# Motor_Control.net
KiCad netlist of a schematic drawn in EAGLE
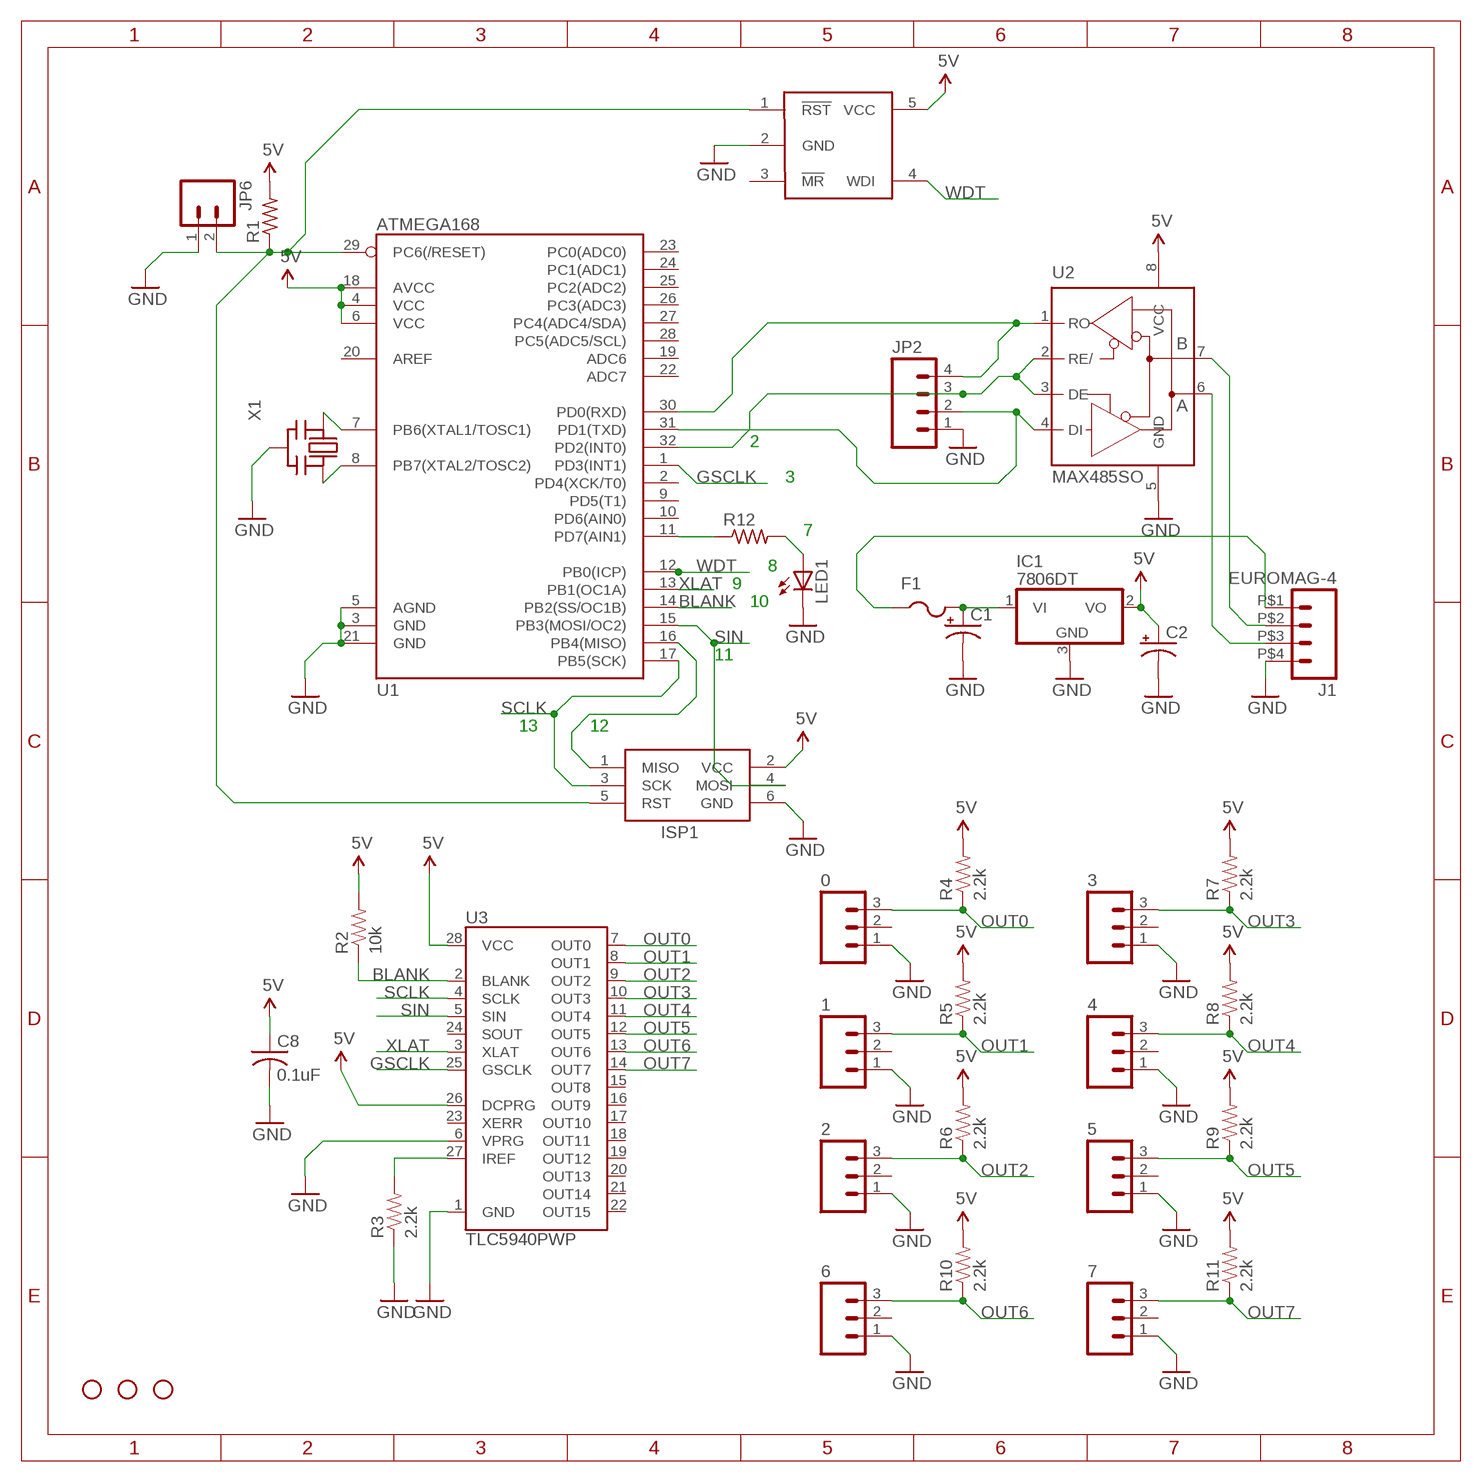
[diagram p0: schematic, sheet 1]
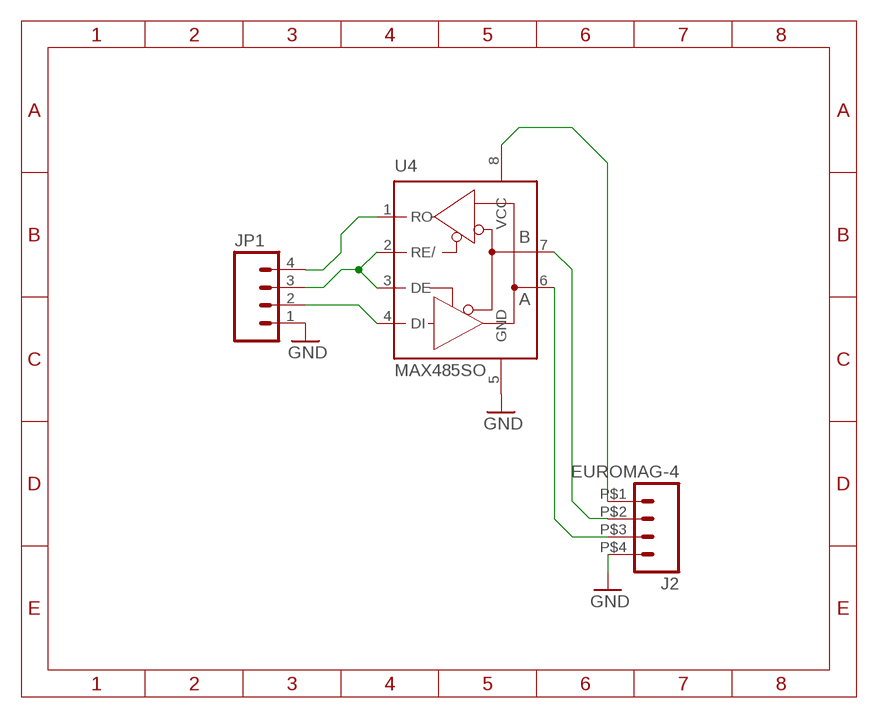
[diagram p1: schematic, sheet 2]

(export (version "E")
  (design (tool "Eeschema 10.0.6"))
  (components
    (comp (ref "0")
      (value "M03PTH")
      (footprint "eagle-import:1X03")
      (libsource (lib "eagle-import") (part "M03PTH"))
    )
    (comp (ref "1")
      (value "M03PTH")
      (footprint "eagle-import:1X03")
      (libsource (lib "eagle-import") (part "M03PTH"))
    )
    (comp (ref "2")
      (value "M03PTH")
      (footprint "eagle-import:1X03")
      (libsource (lib "eagle-import") (part "M03PTH"))
    )
    (comp (ref "3")
      (value "M03PTH")
      (footprint "eagle-import:1X03")
      (libsource (lib "eagle-import") (part "M03PTH"))
    )
    (comp (ref "4")
      (value "M03PTH")
      (footprint "eagle-import:1X03")
      (libsource (lib "eagle-import") (part "M03PTH"))
    )
    (comp (ref "5")
      (value "M03PTH")
      (footprint "eagle-import:1X03")
      (libsource (lib "eagle-import") (part "M03PTH"))
    )
    (comp (ref "6")
      (value "M03PTH")
      (footprint "eagle-import:1X03")
      (libsource (lib "eagle-import") (part "M03PTH"))
    )
    (comp (ref "7")
      (value "M03PTH")
      (footprint "eagle-import:1X03")
      (libsource (lib "eagle-import") (part "M03PTH"))
    )
    (comp (ref "C1")
      (value "CPOL-USCT7343")
      (footprint "eagle-import:CT7343")
      (libsource (lib "eagle-import") (part "CPOL-USCT7343"))
    )
    (comp (ref "C2")
      (value "CPOL-USCT6032")
      (footprint "eagle-import:CT6032")
      (libsource (lib "eagle-import") (part "CPOL-USCT6032"))
    )
    (comp (ref "C8")
      (value "0.1uF")
      (footprint "eagle-import:C0603")
      (libsource (lib "eagle-import") (part "C-USC0603"))
    )
    (comp (ref "F1")
      (value "PTCFUSE-1812")
      (footprint "eagle-import:1812")
      (libsource (lib "eagle-import") (part "PTCFUSE-1812"))
    )
    (comp (ref "IC1")
      (value "7806DT")
      (footprint "eagle-import:TO252")
      (libsource (lib "eagle-import") (part "78DT06"))
    )
    (comp (ref "ISP1")
      (value "AVRISP-6")
      (footprint "eagle-import:AVRISP")
      (libsource (lib "eagle-import") (part "AVRISP-6"))
    )
    (comp (ref "J1")
      (value "EUROMAG-4")
      (footprint "eagle-import:M4")
      (libsource (lib "eagle-import") (part "EUROMAG-4"))
    )
    (comp (ref "JP2")
      (value "M04PTH")
      (footprint "eagle-import:1X04")
      (libsource (lib "eagle-import") (part "M04PTH"))
    )
    (comp (ref "JP3")
      (value "STAND-OFF")
      (footprint "eagle-import:STAND-OFF")
      (libsource (lib "eagle-import") (part "STAND-OFF"))
    )
    (comp (ref "JP4")
      (value "STAND-OFF")
      (footprint "eagle-import:STAND-OFF")
      (libsource (lib "eagle-import") (part "STAND-OFF"))
    )
    (comp (ref "JP5")
      (value "STAND-OFF")
      (footprint "eagle-import:STAND-OFF")
      (libsource (lib "eagle-import") (part "STAND-OFF"))
    )
    (comp (ref "JP6")
      (value "M02LOCK_LONGPADS")
      (footprint "eagle-import:1X02_LOCK_LONGPADS")
      (libsource (lib "eagle-import") (part "M02LOCK_LONGPADS"))
    )
    (comp (ref "LED1")
      (value "LEDCHIPLED_0805")
      (footprint "eagle-import:CHIPLED_0805")
      (libsource (lib "eagle-import") (part "LEDCHIPLED_0805"))
    )
    (comp (ref "R1")
      (value "R-US_M0805")
      (footprint "eagle-import:M0805")
      (libsource (lib "eagle-import") (part "R-US_M0805"))
    )
    (comp (ref "R2")
      (value "10k")
      (footprint "eagle-import:0805")
      (libsource (lib "eagle-import") (part "RESISTOR0805-RES"))
    )
    (comp (ref "R3")
      (value "2.2k")
      (footprint "eagle-import:0805")
      (libsource (lib "eagle-import") (part "RESISTOR0805-RES"))
    )
    (comp (ref "R4")
      (value "2.2k")
      (footprint "eagle-import:0805")
      (libsource (lib "eagle-import") (part "RESISTOR0805-RES"))
    )
    (comp (ref "R5")
      (value "2.2k")
      (footprint "eagle-import:0805")
      (libsource (lib "eagle-import") (part "RESISTOR0805-RES"))
    )
    (comp (ref "R6")
      (value "2.2k")
      (footprint "eagle-import:0805")
      (libsource (lib "eagle-import") (part "RESISTOR0805-RES"))
    )
    (comp (ref "R7")
      (value "2.2k")
      (footprint "eagle-import:0805")
      (libsource (lib "eagle-import") (part "RESISTOR0805-RES"))
    )
    (comp (ref "R8")
      (value "2.2k")
      (footprint "eagle-import:0805")
      (libsource (lib "eagle-import") (part "RESISTOR0805-RES"))
    )
    (comp (ref "R9")
      (value "2.2k")
      (footprint "eagle-import:0805")
      (libsource (lib "eagle-import") (part "RESISTOR0805-RES"))
    )
    (comp (ref "R10")
      (value "2.2k")
      (footprint "eagle-import:0805")
      (libsource (lib "eagle-import") (part "RESISTOR0805-RES"))
    )
    (comp (ref "R11")
      (value "2.2k")
      (footprint "eagle-import:0805")
      (libsource (lib "eagle-import") (part "RESISTOR0805-RES"))
    )
    (comp (ref "R12")
      (value "R-US_M0805")
      (footprint "eagle-import:M0805")
      (libsource (lib "eagle-import") (part "R-US_M0805"))
    )
    (comp (ref "U$18")
      (value "MAX823")
      (footprint "eagle-import:SOT23-5L")
      (libsource (lib "eagle-import") (part "MAX823"))
    )
    (comp (ref "U1")
      (value "ATMEGA168")
      (footprint "eagle-import:TQFP32-08")
      (libsource (lib "eagle-import") (part "ATMEGA168"))
    )
    (comp (ref "U2")
      (value "MAX485SO")
      (footprint "eagle-import:SO08")
      (libsource (lib "eagle-import") (part "MAX485SO"))
    )
    (comp (ref "U3")
      (value "TLC5940PWP")
      (footprint "eagle-import:TSSOP28-GROUNDPAD")
      (libsource (lib "eagle-import") (part "TLC5940PWP"))
    )
    (comp (ref "X1")
      (value "CERMOSCILL-AWCSR")
      (footprint "eagle-import:AWCSR")
      (libsource (lib "eagle-import") (part "CERMOSCILL-AWCSR"))
    )
    (comp (ref "J2")
      (value "EUROMAG-4")
      (footprint "eagle-import:M4")
      (libsource (lib "eagle-import") (part "EUROMAG-4"))
    )
    (comp (ref "JP1")
      (value "M04PTH")
      (footprint "eagle-import:1X04")
      (libsource (lib "eagle-import") (part "M04PTH"))
    )
    (comp (ref "U4")
      (value "MAX485SO")
      (footprint "eagle-import:SO08")
      (libsource (lib "eagle-import") (part "MAX485SO"))
    )
  )
  (nets
    (net (code "1") (name "5V") (class "Default")
      (node (ref "C2") (pin "+") (pinfunction "+_+") (pintype "passive"))
      (node (ref "C8") (pin "1") (pinfunction "1_1") (pintype "passive"))
      (node (ref "IC1") (pin "2") (pinfunction "VO_2") (pintype "passive"))
      (node (ref "ISP1") (pin "2") (pinfunction "VCC_2") (pintype "power_in"))
      (node (ref "R1") (pin "2") (pinfunction "2_2") (pintype "passive"))
      (node (ref "R10") (pin "2") (pinfunction "2_2") (pintype "passive"))
      (node (ref "R11") (pin "2") (pinfunction "2_2") (pintype "passive"))
      (node (ref "R2") (pin "2") (pinfunction "2_2") (pintype "passive"))
      (node (ref "R4") (pin "2") (pinfunction "2_2") (pintype "passive"))
      (node (ref "R5") (pin "2") (pinfunction "2_2") (pintype "passive"))
      (node (ref "R6") (pin "2") (pinfunction "2_2") (pintype "passive"))
      (node (ref "R7") (pin "2") (pinfunction "2_2") (pintype "passive"))
      (node (ref "R8") (pin "2") (pinfunction "2_2") (pintype "passive"))
      (node (ref "R9") (pin "2") (pinfunction "2_2") (pintype "passive"))
      (node (ref "U$18") (pin "5") (pinfunction "VCC_5") (pintype "bidirectional"))
      (node (ref "U1") (pin "18") (pinfunction "AVCC_18") (pintype "bidirectional"))
      (node (ref "U1") (pin "4") (pinfunction "VCC_4") (pintype "bidirectional"))
      (node (ref "U1") (pin "6") (pinfunction "VCC_6") (pintype "bidirectional"))
      (node (ref "U2") (pin "8") (pinfunction "VCC_8") (pintype "bidirectional"))
      (node (ref "U3") (pin "26") (pinfunction "DCPRG_26") (pintype "bidirectional"))
      (node (ref "U3") (pin "28") (pinfunction "VCC_28") (pintype "bidirectional"))
    )
    (net (code "2") (name "BLANK") (class "Default")
      (node (ref "R2") (pin "1") (pinfunction "1_1") (pintype "passive"))
      (node (ref "U1") (pin "14") (pinfunction "PB2(SS/OC1B)_14") (pintype "bidirectional"))
      (node (ref "U3") (pin "2") (pinfunction "BLANK_2") (pintype "bidirectional"))
    )
    (net (code "3") (name "GND") (class "Default")
      (node (ref "0") (pin "1") (pinfunction "1_1") (pintype "passive"))
      (node (ref "1") (pin "1") (pinfunction "1_1") (pintype "passive"))
      (node (ref "2") (pin "1") (pinfunction "1_1") (pintype "passive"))
      (node (ref "3") (pin "1") (pinfunction "1_1") (pintype "passive"))
      (node (ref "4") (pin "1") (pinfunction "1_1") (pintype "passive"))
      (node (ref "5") (pin "1") (pinfunction "1_1") (pintype "passive"))
      (node (ref "6") (pin "1") (pinfunction "1_1") (pintype "passive"))
      (node (ref "7") (pin "1") (pinfunction "1_1") (pintype "passive"))
      (node (ref "C1") (pin "-") (pinfunction "-_-") (pintype "passive"))
      (node (ref "C2") (pin "-") (pinfunction "-_-") (pintype "passive"))
      (node (ref "C8") (pin "2") (pinfunction "2_2") (pintype "passive"))
      (node (ref "IC1") (pin "3") (pinfunction "GND_3") (pintype "passive"))
      (node (ref "ISP1") (pin "6") (pinfunction "GND_6") (pintype "power_in"))
      (node (ref "J1") (pin "P$4") (pinfunction "4_P$4") (pintype "passive"))
      (node (ref "J2") (pin "P$4") (pinfunction "4_P$4") (pintype "passive"))
      (node (ref "JP1") (pin "1") (pinfunction "1_1") (pintype "passive"))
      (node (ref "JP2") (pin "1") (pinfunction "1_1") (pintype "passive"))
      (node (ref "JP6") (pin "1") (pinfunction "1_1") (pintype "passive"))
      (node (ref "LED1") (pin "C") (pinfunction "C_C") (pintype "passive"))
      (node (ref "R3") (pin "1") (pinfunction "1_1") (pintype "passive"))
      (node (ref "U$18") (pin "2") (pinfunction "GND_2") (pintype "bidirectional"))
      (node (ref "U1") (pin "21") (pinfunction "GND_21") (pintype "bidirectional"))
      (node (ref "U1") (pin "3") (pinfunction "GND_3") (pintype "bidirectional"))
      (node (ref "U1") (pin "5") (pinfunction "AGND_5") (pintype "bidirectional"))
      (node (ref "U2") (pin "5") (pinfunction "GND_5") (pintype "bidirectional"))
      (node (ref "U3") (pin "1") (pinfunction "GND_1") (pintype "bidirectional"))
      (node (ref "U3") (pin "6") (pinfunction "VPRG_6") (pintype "bidirectional"))
      (node (ref "U4") (pin "5") (pinfunction "GND_5") (pintype "bidirectional"))
      (node (ref "X1") (pin "2") (pinfunction "GND_2") (pintype "bidirectional"))
    )
    (net (code "4") (name "GSCLK") (class "Default")
      (node (ref "U1") (pin "1") (pinfunction "PD3(INT1)_1") (pintype "bidirectional"))
      (node (ref "U3") (pin "25") (pinfunction "GSCLK_25") (pintype "bidirectional"))
    )
    (net (code "5") (name "Net-(IC1-VI)") (class "Default")
      (node (ref "C1") (pin "+") (pinfunction "+_+") (pintype "passive"))
      (node (ref "F1") (pin "2") (pinfunction "2_2") (pintype "passive"))
      (node (ref "IC1") (pin "1") (pinfunction "VI_1") (pintype "input"))
    )
    (net (code "6") (name "Net-(ISP1-MISO)") (class "Default")
      (node (ref "ISP1") (pin "1") (pinfunction "MISO_1") (pintype "input"))
      (node (ref "U1") (pin "16") (pinfunction "PB4(MISO)_16") (pintype "bidirectional"))
    )
    (net (code "7") (name "Net-(ISP1-RST)") (class "Default")
      (node (ref "ISP1") (pin "5") (pinfunction "RST_5") (pintype "output"))
      (node (ref "JP6") (pin "2") (pinfunction "2_2") (pintype "passive"))
      (node (ref "R1") (pin "1") (pinfunction "1_1") (pintype "passive"))
      (node (ref "U$18") (pin "1") (pinfunction "~{RST}_1") (pintype "bidirectional"))
      (node (ref "U1") (pin "29") (pinfunction "PC6(/RESET)_29") (pintype "bidirectional"))
    )
    (net (code "8") (name "Net-(J1-1)") (class "Default")
      (node (ref "F1") (pin "1") (pinfunction "1_1") (pintype "passive"))
      (node (ref "J1") (pin "P$1") (pinfunction "1_P$1") (pintype "passive"))
    )
    (net (code "9") (name "Net-(J1-2)") (class "Default")
      (node (ref "J1") (pin "P$2") (pinfunction "2_P$2") (pintype "passive"))
      (node (ref "U2") (pin "7") (pinfunction "B_7") (pintype "passive"))
    )
    (net (code "10") (name "Net-(J1-3)") (class "Default")
      (node (ref "J1") (pin "P$3") (pinfunction "3_P$3") (pintype "passive"))
      (node (ref "U2") (pin "6") (pinfunction "A_6") (pintype "passive"))
    )
    (net (code "11") (name "Net-(J2-1)") (class "Default")
      (node (ref "J2") (pin "P$1") (pinfunction "1_P$1") (pintype "passive"))
      (node (ref "U4") (pin "8") (pinfunction "VCC_8") (pintype "bidirectional"))
    )
    (net (code "12") (name "Net-(J2-2)") (class "Default")
      (node (ref "J2") (pin "P$2") (pinfunction "2_P$2") (pintype "passive"))
      (node (ref "U4") (pin "7") (pinfunction "B_7") (pintype "passive"))
    )
    (net (code "13") (name "Net-(J2-3)") (class "Default")
      (node (ref "J2") (pin "P$3") (pinfunction "3_P$3") (pintype "passive"))
      (node (ref "U4") (pin "6") (pinfunction "A_6") (pintype "passive"))
    )
    (net (code "14") (name "Net-(LED1-PadA)") (class "Default")
      (node (ref "LED1") (pin "A") (pinfunction "A_A") (pintype "passive"))
      (node (ref "R12") (pin "2") (pinfunction "2_2") (pintype "passive"))
    )
    (net (code "15") (name "Net-(U1-PB6(XTAL1{slash}TOSC1))") (class "Default")
      (node (ref "U1") (pin "7") (pinfunction "PB6(XTAL1/TOSC1)_7") (pintype "bidirectional"))
      (node (ref "X1") (pin "1") (pinfunction "IN_1") (pintype "bidirectional"))
    )
    (net (code "16") (name "Net-(U1-PB7(XTAL2{slash}TOSC2))") (class "Default")
      (node (ref "U1") (pin "8") (pinfunction "PB7(XTAL2/TOSC2)_8") (pintype "bidirectional"))
      (node (ref "X1") (pin "3") (pinfunction "OUT_3") (pintype "bidirectional"))
    )
    (net (code "17") (name "Net-(U1-PD0(RXD))") (class "Default")
      (node (ref "JP2") (pin "4") (pinfunction "4_4") (pintype "passive"))
      (node (ref "U1") (pin "30") (pinfunction "PD0(RXD)_30") (pintype "bidirectional"))
      (node (ref "U2") (pin "1") (pinfunction "RO_1") (pintype "output"))
    )
    (net (code "18") (name "Net-(U1-PD1(TXD))") (class "Default")
      (node (ref "JP2") (pin "2") (pinfunction "2_2") (pintype "passive"))
      (node (ref "U1") (pin "31") (pinfunction "PD1(TXD)_31") (pintype "bidirectional"))
      (node (ref "U2") (pin "4") (pinfunction "DI_4") (pintype "input"))
    )
    (net (code "19") (name "Net-(U1-PD2(INT0))") (class "Default")
      (node (ref "JP2") (pin "3") (pinfunction "3_3") (pintype "passive"))
      (node (ref "U1") (pin "32") (pinfunction "PD2(INT0)_32") (pintype "bidirectional"))
      (node (ref "U2") (pin "2") (pinfunction "RE/_2") (pintype "input"))
      (node (ref "U2") (pin "3") (pinfunction "DE_3") (pintype "input"))
    )
    (net (code "20") (name "Net-(U1-PD7(AIN1))") (class "Default")
      (node (ref "R12") (pin "1") (pinfunction "1_1") (pintype "passive"))
      (node (ref "U1") (pin "11") (pinfunction "PD7(AIN1)_11") (pintype "bidirectional"))
    )
    (net (code "21") (name "Net-(U3-IREF)") (class "Default")
      (node (ref "R3") (pin "2") (pinfunction "2_2") (pintype "passive"))
      (node (ref "U3") (pin "27") (pinfunction "IREF_27") (pintype "bidirectional"))
    )
    (net (code "22") (name "Net-(U4-DE)") (class "Default")
      (node (ref "JP1") (pin "3") (pinfunction "3_3") (pintype "passive"))
      (node (ref "U4") (pin "2") (pinfunction "RE/_2") (pintype "input"))
      (node (ref "U4") (pin "3") (pinfunction "DE_3") (pintype "input"))
    )
    (net (code "23") (name "Net-(U4-DI)") (class "Default")
      (node (ref "JP1") (pin "2") (pinfunction "2_2") (pintype "passive"))
      (node (ref "U4") (pin "4") (pinfunction "DI_4") (pintype "input"))
    )
    (net (code "24") (name "Net-(U4-RO)") (class "Default")
      (node (ref "JP1") (pin "4") (pinfunction "4_4") (pintype "passive"))
      (node (ref "U4") (pin "1") (pinfunction "RO_1") (pintype "output"))
    )
    (net (code "25") (name "OUT0") (class "Default")
      (node (ref "0") (pin "3") (pinfunction "3_3") (pintype "passive"))
      (node (ref "R4") (pin "1") (pinfunction "1_1") (pintype "passive"))
      (node (ref "U3") (pin "7") (pinfunction "OUT0_7") (pintype "bidirectional"))
    )
    (net (code "26") (name "OUT1") (class "Default")
      (node (ref "1") (pin "3") (pinfunction "3_3") (pintype "passive"))
      (node (ref "R5") (pin "1") (pinfunction "1_1") (pintype "passive"))
      (node (ref "U3") (pin "8") (pinfunction "OUT1_8") (pintype "bidirectional"))
    )
    (net (code "27") (name "OUT2") (class "Default")
      (node (ref "2") (pin "3") (pinfunction "3_3") (pintype "passive"))
      (node (ref "R6") (pin "1") (pinfunction "1_1") (pintype "passive"))
      (node (ref "U3") (pin "9") (pinfunction "OUT2_9") (pintype "bidirectional"))
    )
    (net (code "28") (name "OUT3") (class "Default")
      (node (ref "3") (pin "3") (pinfunction "3_3") (pintype "passive"))
      (node (ref "R7") (pin "1") (pinfunction "1_1") (pintype "passive"))
      (node (ref "U3") (pin "10") (pinfunction "OUT3_10") (pintype "bidirectional"))
    )
    (net (code "29") (name "OUT4") (class "Default")
      (node (ref "4") (pin "3") (pinfunction "3_3") (pintype "passive"))
      (node (ref "R8") (pin "1") (pinfunction "1_1") (pintype "passive"))
      (node (ref "U3") (pin "11") (pinfunction "OUT4_11") (pintype "bidirectional"))
    )
    (net (code "30") (name "OUT5") (class "Default")
      (node (ref "5") (pin "3") (pinfunction "3_3") (pintype "passive"))
      (node (ref "R9") (pin "1") (pinfunction "1_1") (pintype "passive"))
      (node (ref "U3") (pin "12") (pinfunction "OUT5_12") (pintype "bidirectional"))
    )
    (net (code "31") (name "OUT6") (class "Default")
      (node (ref "6") (pin "3") (pinfunction "3_3") (pintype "passive"))
      (node (ref "R10") (pin "1") (pinfunction "1_1") (pintype "passive"))
      (node (ref "U3") (pin "13") (pinfunction "OUT6_13") (pintype "bidirectional"))
    )
    (net (code "32") (name "OUT7") (class "Default")
      (node (ref "7") (pin "3") (pinfunction "3_3") (pintype "passive"))
      (node (ref "R11") (pin "1") (pinfunction "1_1") (pintype "passive"))
      (node (ref "U3") (pin "14") (pinfunction "OUT7_14") (pintype "bidirectional"))
    )
    (net (code "33") (name "SCLK") (class "Default")
      (node (ref "ISP1") (pin "3") (pinfunction "SCK_3") (pintype "output"))
      (node (ref "U1") (pin "17") (pinfunction "PB5(SCK)_17") (pintype "bidirectional"))
      (node (ref "U3") (pin "4") (pinfunction "SCLK_4") (pintype "bidirectional"))
    )
    (net (code "34") (name "SIN") (class "Default")
      (node (ref "ISP1") (pin "4") (pinfunction "MOSI_4") (pintype "output"))
      (node (ref "U1") (pin "15") (pinfunction "PB3(MOSI/OC2)_15") (pintype "bidirectional"))
      (node (ref "U3") (pin "5") (pinfunction "SIN_5") (pintype "bidirectional"))
    )
    (net (code "35") (name "WDT") (class "Default")
      (node (ref "U$18") (pin "4") (pinfunction "WDI_4") (pintype "bidirectional"))
      (node (ref "U1") (pin "12") (pinfunction "PB0(ICP)_12") (pintype "bidirectional"))
    )
    (net (code "36") (name "XLAT") (class "Default")
      (node (ref "U1") (pin "13") (pinfunction "PB1(OC1A)_13") (pintype "bidirectional"))
      (node (ref "U3") (pin "3") (pinfunction "XLAT_3") (pintype "bidirectional"))
    )
    (net (code "37") (name "unconnected-(0-Pad2)") (class "Default")
      (node (ref "0") (pin "2") (pinfunction "2_2") (pintype "passive"))
    )
    (net (code "38") (name "unconnected-(1-Pad2)") (class "Default")
      (node (ref "1") (pin "2") (pinfunction "2_2") (pintype "passive"))
    )
    (net (code "39") (name "unconnected-(2-Pad2)") (class "Default")
      (node (ref "2") (pin "2") (pinfunction "2_2") (pintype "passive"))
    )
    (net (code "40") (name "unconnected-(3-Pad2)") (class "Default")
      (node (ref "3") (pin "2") (pinfunction "2_2") (pintype "passive"))
    )
    (net (code "41") (name "unconnected-(4-Pad2)") (class "Default")
      (node (ref "4") (pin "2") (pinfunction "2_2") (pintype "passive"))
    )
    (net (code "42") (name "unconnected-(5-Pad2)") (class "Default")
      (node (ref "5") (pin "2") (pinfunction "2_2") (pintype "passive"))
    )
    (net (code "43") (name "unconnected-(6-Pad2)") (class "Default")
      (node (ref "6") (pin "2") (pinfunction "2_2") (pintype "passive"))
    )
    (net (code "44") (name "unconnected-(7-Pad2)") (class "Default")
      (node (ref "7") (pin "2") (pinfunction "2_2") (pintype "passive"))
    )
    (net (code "45") (name "unconnected-(U$18-~{MR}-Pad3)") (class "Default")
      (node (ref "U$18") (pin "3") (pinfunction "~{MR}_3") (pintype "bidirectional"))
    )
    (net (code "46") (name "unconnected-(U1-ADC6-Pad19)") (class "Default")
      (node (ref "U1") (pin "19") (pinfunction "ADC6_19") (pintype "bidirectional"))
    )
    (net (code "47") (name "unconnected-(U1-ADC7-Pad22)") (class "Default")
      (node (ref "U1") (pin "22") (pinfunction "ADC7_22") (pintype "bidirectional"))
    )
    (net (code "48") (name "unconnected-(U1-AREF-Pad20)") (class "Default")
      (node (ref "U1") (pin "20") (pinfunction "AREF_20") (pintype "bidirectional"))
    )
    (net (code "49") (name "unconnected-(U1-PC0(ADC0)-Pad23)") (class "Default")
      (node (ref "U1") (pin "23") (pinfunction "PC0(ADC0)_23") (pintype "bidirectional"))
    )
    (net (code "50") (name "unconnected-(U1-PC1(ADC1)-Pad24)") (class "Default")
      (node (ref "U1") (pin "24") (pinfunction "PC1(ADC1)_24") (pintype "bidirectional"))
    )
    (net (code "51") (name "unconnected-(U1-PC2(ADC2)-Pad25)") (class "Default")
      (node (ref "U1") (pin "25") (pinfunction "PC2(ADC2)_25") (pintype "bidirectional"))
    )
    (net (code "52") (name "unconnected-(U1-PC3(ADC3)-Pad26)") (class "Default")
      (node (ref "U1") (pin "26") (pinfunction "PC3(ADC3)_26") (pintype "bidirectional"))
    )
    (net (code "53") (name "unconnected-(U1-PC4(ADC4{slash}SDA)-Pad27)") (class "Default")
      (node (ref "U1") (pin "27") (pinfunction "PC4(ADC4/SDA)_27") (pintype "bidirectional"))
    )
    (net (code "54") (name "unconnected-(U1-PC5(ADC5{slash}SCL)-Pad28)") (class "Default")
      (node (ref "U1") (pin "28") (pinfunction "PC5(ADC5/SCL)_28") (pintype "bidirectional"))
    )
    (net (code "55") (name "unconnected-(U1-PD4(XCK{slash}T0)-Pad2)") (class "Default")
      (node (ref "U1") (pin "2") (pinfunction "PD4(XCK/T0)_2") (pintype "bidirectional"))
    )
    (net (code "56") (name "unconnected-(U1-PD5(T1)-Pad9)") (class "Default")
      (node (ref "U1") (pin "9") (pinfunction "PD5(T1)_9") (pintype "bidirectional"))
    )
    (net (code "57") (name "unconnected-(U1-PD6(AIN0)-Pad10)") (class "Default")
      (node (ref "U1") (pin "10") (pinfunction "PD6(AIN0)_10") (pintype "bidirectional"))
    )
    (net (code "58") (name "unconnected-(U3-OUT8-Pad15)") (class "Default")
      (node (ref "U3") (pin "15") (pinfunction "OUT8_15") (pintype "bidirectional"))
    )
    (net (code "59") (name "unconnected-(U3-OUT9-Pad16)") (class "Default")
      (node (ref "U3") (pin "16") (pinfunction "OUT9_16") (pintype "bidirectional"))
    )
    (net (code "60") (name "unconnected-(U3-OUT10-Pad17)") (class "Default")
      (node (ref "U3") (pin "17") (pinfunction "OUT10_17") (pintype "bidirectional"))
    )
    (net (code "61") (name "unconnected-(U3-OUT11-Pad18)") (class "Default")
      (node (ref "U3") (pin "18") (pinfunction "OUT11_18") (pintype "bidirectional"))
    )
    (net (code "62") (name "unconnected-(U3-OUT12-Pad19)") (class "Default")
      (node (ref "U3") (pin "19") (pinfunction "OUT12_19") (pintype "bidirectional"))
    )
    (net (code "63") (name "unconnected-(U3-OUT13-Pad20)") (class "Default")
      (node (ref "U3") (pin "20") (pinfunction "OUT13_20") (pintype "bidirectional"))
    )
    (net (code "64") (name "unconnected-(U3-OUT14-Pad21)") (class "Default")
      (node (ref "U3") (pin "21") (pinfunction "OUT14_21") (pintype "bidirectional"))
    )
    (net (code "65") (name "unconnected-(U3-OUT15-Pad22)") (class "Default")
      (node (ref "U3") (pin "22") (pinfunction "OUT15_22") (pintype "bidirectional"))
    )
    (net (code "66") (name "unconnected-(U3-SOUT-Pad24)") (class "Default")
      (node (ref "U3") (pin "24") (pinfunction "SOUT_24") (pintype "bidirectional"))
    )
    (net (code "67") (name "unconnected-(U3-XERR-Pad23)") (class "Default")
      (node (ref "U3") (pin "23") (pinfunction "XERR_23") (pintype "bidirectional"))
    )
  )
)
